# 4-layer-microstrip-nomask-osh.net
KiCad netlist of a schematic drawn in EAGLE
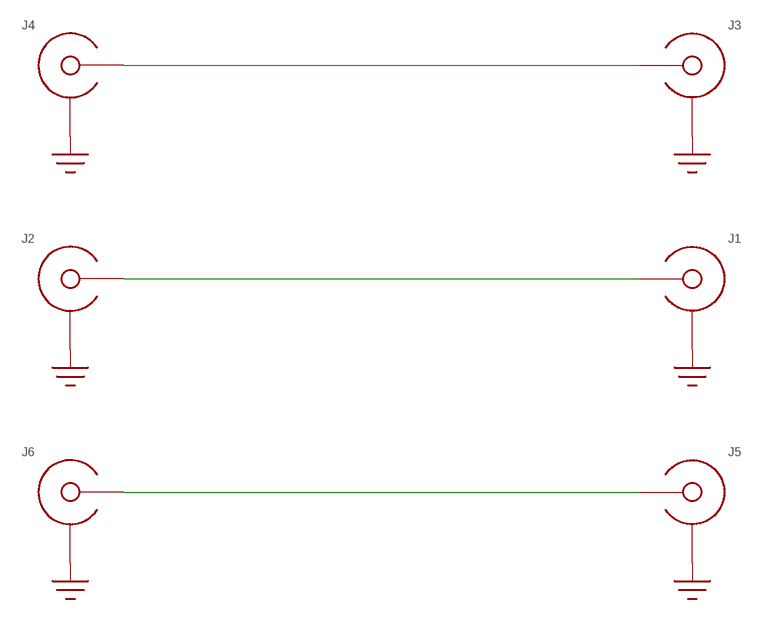
[diagram p0: schematic, sheet 1]

(export (version "E")
  (design (tool "Eeschema 10.0.6"))
  (components
    (comp (ref "J1")
      (value "SMA-EDGE-LAUNCH4L-4020-TAPER-FIXED")
      (footprint "eagle-import:SMA_EDGE_LAUNCH_4L_4020_TAPER_FIXED")
      (libsource (lib "eagle-import") (part "SMA-EDGE-LAUNCH4L-4020-TAPER-FIXED"))
    )
    (comp (ref "J2")
      (value "SMA-EDGE-LAUNCH4L-4020-TAPER-FIXED")
      (footprint "eagle-import:SMA_EDGE_LAUNCH_4L_4020_TAPER_FIXED")
      (libsource (lib "eagle-import") (part "SMA-EDGE-LAUNCH4L-4020-TAPER-FIXED"))
    )
    (comp (ref "J3")
      (value "SMA-EDGE-LAUNCH4L-4020-TAPER-FIXED")
      (footprint "eagle-import:SMA_EDGE_LAUNCH_4L_4020_TAPER_FIXED")
      (libsource (lib "eagle-import") (part "SMA-EDGE-LAUNCH4L-4020-TAPER-FIXED"))
    )
    (comp (ref "J4")
      (value "SMA-EDGE-LAUNCH4L-4020-TAPER-FIXED")
      (footprint "eagle-import:SMA_EDGE_LAUNCH_4L_4020_TAPER_FIXED")
      (libsource (lib "eagle-import") (part "SMA-EDGE-LAUNCH4L-4020-TAPER-FIXED"))
    )
    (comp (ref "J5")
      (value "SMA-EDGE-LAUNCH4L-4020-TAPER-FIXED")
      (footprint "eagle-import:SMA_EDGE_LAUNCH_4L_4020_TAPER_FIXED")
      (libsource (lib "eagle-import") (part "SMA-EDGE-LAUNCH4L-4020-TAPER-FIXED"))
    )
    (comp (ref "J6")
      (value "SMA-EDGE-LAUNCH4L-4020-TAPER-FIXED")
      (footprint "eagle-import:SMA_EDGE_LAUNCH_4L_4020_TAPER_FIXED")
      (libsource (lib "eagle-import") (part "SMA-EDGE-LAUNCH4L-4020-TAPER-FIXED"))
    )
  )
  (nets
    (net (code "1") (name "GND") (class "Default")
      (node (ref "J1") (pin "BOTTOM_GND") (pinfunction "SHIELD_BOTTOM_GND") (pintype "bidirectional"))
      (node (ref "J1") (pin "GND@1") (pinfunction "SHIELD_GND@1") (pintype "bidirectional"))
      (node (ref "J1") (pin "GND@14") (pinfunction "SHIELD_GND@14") (pintype "bidirectional"))
      (node (ref "J1") (pin "GND@15") (pinfunction "SHIELD_GND@15") (pintype "bidirectional"))
      (node (ref "J1") (pin "GND@16") (pinfunction "SHIELD_GND@16") (pintype "bidirectional"))
      (node (ref "J1") (pin "GND@17") (pinfunction "SHIELD_GND@17") (pintype "bidirectional"))
      (node (ref "J1") (pin "GND@2") (pinfunction "SHIELD_GND@2") (pintype "bidirectional"))
      (node (ref "J1") (pin "GND@3") (pinfunction "SHIELD_GND@3") (pintype "bidirectional"))
      (node (ref "J1") (pin "GND@4") (pinfunction "SHIELD_GND@4") (pintype "bidirectional"))
      (node (ref "J1") (pin "GND@5") (pinfunction "SHIELD_GND@5") (pintype "bidirectional"))
      (node (ref "J1") (pin "GND@6") (pinfunction "SHIELD_GND@6") (pintype "bidirectional"))
      (node (ref "J1") (pin "GND@7") (pinfunction "SHIELD_GND@7") (pintype "bidirectional"))
      (node (ref "J1") (pin "GND@8") (pinfunction "SHIELD_GND@8") (pintype "bidirectional"))
      (node (ref "J1") (pin "GND_PAD1") (pinfunction "SHIELD_GND_PAD1") (pintype "bidirectional"))
      (node (ref "J1") (pin "GND_PAD2") (pinfunction "SHIELD_GND_PAD2") (pintype "bidirectional"))
      (node (ref "J1") (pin "P$1") (pinfunction "SHIELD_P$1") (pintype "bidirectional"))
      (node (ref "J1") (pin "P$2") (pinfunction "SHIELD_P$2") (pintype "bidirectional"))
      (node (ref "J2") (pin "BOTTOM_GND") (pinfunction "SHIELD_BOTTOM_GND") (pintype "bidirectional"))
      (node (ref "J2") (pin "GND@1") (pinfunction "SHIELD_GND@1") (pintype "bidirectional"))
      (node (ref "J2") (pin "GND@14") (pinfunction "SHIELD_GND@14") (pintype "bidirectional"))
      (node (ref "J2") (pin "GND@15") (pinfunction "SHIELD_GND@15") (pintype "bidirectional"))
      (node (ref "J2") (pin "GND@16") (pinfunction "SHIELD_GND@16") (pintype "bidirectional"))
      (node (ref "J2") (pin "GND@17") (pinfunction "SHIELD_GND@17") (pintype "bidirectional"))
      (node (ref "J2") (pin "GND@2") (pinfunction "SHIELD_GND@2") (pintype "bidirectional"))
      (node (ref "J2") (pin "GND@3") (pinfunction "SHIELD_GND@3") (pintype "bidirectional"))
      (node (ref "J2") (pin "GND@4") (pinfunction "SHIELD_GND@4") (pintype "bidirectional"))
      (node (ref "J2") (pin "GND@5") (pinfunction "SHIELD_GND@5") (pintype "bidirectional"))
      (node (ref "J2") (pin "GND@6") (pinfunction "SHIELD_GND@6") (pintype "bidirectional"))
      (node (ref "J2") (pin "GND@7") (pinfunction "SHIELD_GND@7") (pintype "bidirectional"))
      (node (ref "J2") (pin "GND@8") (pinfunction "SHIELD_GND@8") (pintype "bidirectional"))
      (node (ref "J2") (pin "GND_PAD1") (pinfunction "SHIELD_GND_PAD1") (pintype "bidirectional"))
      (node (ref "J2") (pin "GND_PAD2") (pinfunction "SHIELD_GND_PAD2") (pintype "bidirectional"))
      (node (ref "J2") (pin "P$1") (pinfunction "SHIELD_P$1") (pintype "bidirectional"))
      (node (ref "J2") (pin "P$2") (pinfunction "SHIELD_P$2") (pintype "bidirectional"))
      (node (ref "J3") (pin "BOTTOM_GND") (pinfunction "SHIELD_BOTTOM_GND") (pintype "bidirectional"))
      (node (ref "J3") (pin "GND@1") (pinfunction "SHIELD_GND@1") (pintype "bidirectional"))
      (node (ref "J3") (pin "GND@14") (pinfunction "SHIELD_GND@14") (pintype "bidirectional"))
      (node (ref "J3") (pin "GND@15") (pinfunction "SHIELD_GND@15") (pintype "bidirectional"))
      (node (ref "J3") (pin "GND@16") (pinfunction "SHIELD_GND@16") (pintype "bidirectional"))
      (node (ref "J3") (pin "GND@17") (pinfunction "SHIELD_GND@17") (pintype "bidirectional"))
      (node (ref "J3") (pin "GND@2") (pinfunction "SHIELD_GND@2") (pintype "bidirectional"))
      (node (ref "J3") (pin "GND@3") (pinfunction "SHIELD_GND@3") (pintype "bidirectional"))
      (node (ref "J3") (pin "GND@4") (pinfunction "SHIELD_GND@4") (pintype "bidirectional"))
      (node (ref "J3") (pin "GND@5") (pinfunction "SHIELD_GND@5") (pintype "bidirectional"))
      (node (ref "J3") (pin "GND@6") (pinfunction "SHIELD_GND@6") (pintype "bidirectional"))
      (node (ref "J3") (pin "GND@7") (pinfunction "SHIELD_GND@7") (pintype "bidirectional"))
      (node (ref "J3") (pin "GND@8") (pinfunction "SHIELD_GND@8") (pintype "bidirectional"))
      (node (ref "J3") (pin "GND_PAD1") (pinfunction "SHIELD_GND_PAD1") (pintype "bidirectional"))
      (node (ref "J3") (pin "GND_PAD2") (pinfunction "SHIELD_GND_PAD2") (pintype "bidirectional"))
      (node (ref "J3") (pin "P$1") (pinfunction "SHIELD_P$1") (pintype "bidirectional"))
      (node (ref "J3") (pin "P$2") (pinfunction "SHIELD_P$2") (pintype "bidirectional"))
      (node (ref "J4") (pin "BOTTOM_GND") (pinfunction "SHIELD_BOTTOM_GND") (pintype "bidirectional"))
      (node (ref "J4") (pin "GND@1") (pinfunction "SHIELD_GND@1") (pintype "bidirectional"))
      (node (ref "J4") (pin "GND@14") (pinfunction "SHIELD_GND@14") (pintype "bidirectional"))
      (node (ref "J4") (pin "GND@15") (pinfunction "SHIELD_GND@15") (pintype "bidirectional"))
      (node (ref "J4") (pin "GND@16") (pinfunction "SHIELD_GND@16") (pintype "bidirectional"))
      (node (ref "J4") (pin "GND@17") (pinfunction "SHIELD_GND@17") (pintype "bidirectional"))
      (node (ref "J4") (pin "GND@2") (pinfunction "SHIELD_GND@2") (pintype "bidirectional"))
      (node (ref "J4") (pin "GND@3") (pinfunction "SHIELD_GND@3") (pintype "bidirectional"))
      (node (ref "J4") (pin "GND@4") (pinfunction "SHIELD_GND@4") (pintype "bidirectional"))
      (node (ref "J4") (pin "GND@5") (pinfunction "SHIELD_GND@5") (pintype "bidirectional"))
      (node (ref "J4") (pin "GND@6") (pinfunction "SHIELD_GND@6") (pintype "bidirectional"))
      (node (ref "J4") (pin "GND@7") (pinfunction "SHIELD_GND@7") (pintype "bidirectional"))
      (node (ref "J4") (pin "GND@8") (pinfunction "SHIELD_GND@8") (pintype "bidirectional"))
      (node (ref "J4") (pin "GND_PAD1") (pinfunction "SHIELD_GND_PAD1") (pintype "bidirectional"))
      (node (ref "J4") (pin "GND_PAD2") (pinfunction "SHIELD_GND_PAD2") (pintype "bidirectional"))
      (node (ref "J4") (pin "P$1") (pinfunction "SHIELD_P$1") (pintype "bidirectional"))
      (node (ref "J4") (pin "P$2") (pinfunction "SHIELD_P$2") (pintype "bidirectional"))
      (node (ref "J5") (pin "BOTTOM_GND") (pinfunction "SHIELD_BOTTOM_GND") (pintype "bidirectional"))
      (node (ref "J5") (pin "GND@1") (pinfunction "SHIELD_GND@1") (pintype "bidirectional"))
      (node (ref "J5") (pin "GND@14") (pinfunction "SHIELD_GND@14") (pintype "bidirectional"))
      (node (ref "J5") (pin "GND@15") (pinfunction "SHIELD_GND@15") (pintype "bidirectional"))
      (node (ref "J5") (pin "GND@16") (pinfunction "SHIELD_GND@16") (pintype "bidirectional"))
      (node (ref "J5") (pin "GND@17") (pinfunction "SHIELD_GND@17") (pintype "bidirectional"))
      (node (ref "J5") (pin "GND@2") (pinfunction "SHIELD_GND@2") (pintype "bidirectional"))
      (node (ref "J5") (pin "GND@3") (pinfunction "SHIELD_GND@3") (pintype "bidirectional"))
      (node (ref "J5") (pin "GND@4") (pinfunction "SHIELD_GND@4") (pintype "bidirectional"))
      (node (ref "J5") (pin "GND@5") (pinfunction "SHIELD_GND@5") (pintype "bidirectional"))
      (node (ref "J5") (pin "GND@6") (pinfunction "SHIELD_GND@6") (pintype "bidirectional"))
      (node (ref "J5") (pin "GND@7") (pinfunction "SHIELD_GND@7") (pintype "bidirectional"))
      (node (ref "J5") (pin "GND@8") (pinfunction "SHIELD_GND@8") (pintype "bidirectional"))
      (node (ref "J5") (pin "GND_PAD1") (pinfunction "SHIELD_GND_PAD1") (pintype "bidirectional"))
      (node (ref "J5") (pin "GND_PAD2") (pinfunction "SHIELD_GND_PAD2") (pintype "bidirectional"))
      (node (ref "J5") (pin "P$1") (pinfunction "SHIELD_P$1") (pintype "bidirectional"))
      (node (ref "J5") (pin "P$2") (pinfunction "SHIELD_P$2") (pintype "bidirectional"))
      (node (ref "J6") (pin "BOTTOM_GND") (pinfunction "SHIELD_BOTTOM_GND") (pintype "bidirectional"))
      (node (ref "J6") (pin "GND@1") (pinfunction "SHIELD_GND@1") (pintype "bidirectional"))
      (node (ref "J6") (pin "GND@14") (pinfunction "SHIELD_GND@14") (pintype "bidirectional"))
      (node (ref "J6") (pin "GND@15") (pinfunction "SHIELD_GND@15") (pintype "bidirectional"))
      (node (ref "J6") (pin "GND@16") (pinfunction "SHIELD_GND@16") (pintype "bidirectional"))
      (node (ref "J6") (pin "GND@17") (pinfunction "SHIELD_GND@17") (pintype "bidirectional"))
      (node (ref "J6") (pin "GND@2") (pinfunction "SHIELD_GND@2") (pintype "bidirectional"))
      (node (ref "J6") (pin "GND@3") (pinfunction "SHIELD_GND@3") (pintype "bidirectional"))
      (node (ref "J6") (pin "GND@4") (pinfunction "SHIELD_GND@4") (pintype "bidirectional"))
      (node (ref "J6") (pin "GND@5") (pinfunction "SHIELD_GND@5") (pintype "bidirectional"))
      (node (ref "J6") (pin "GND@6") (pinfunction "SHIELD_GND@6") (pintype "bidirectional"))
      (node (ref "J6") (pin "GND@7") (pinfunction "SHIELD_GND@7") (pintype "bidirectional"))
      (node (ref "J6") (pin "GND@8") (pinfunction "SHIELD_GND@8") (pintype "bidirectional"))
      (node (ref "J6") (pin "GND_PAD1") (pinfunction "SHIELD_GND_PAD1") (pintype "bidirectional"))
      (node (ref "J6") (pin "GND_PAD2") (pinfunction "SHIELD_GND_PAD2") (pintype "bidirectional"))
      (node (ref "J6") (pin "P$1") (pinfunction "SHIELD_P$1") (pintype "bidirectional"))
      (node (ref "J6") (pin "P$2") (pinfunction "SHIELD_P$2") (pintype "bidirectional"))
    )
    (net (code "2") (name "Net-(J1-CENTER-PadCENTER@1)") (class "Default")
      (node (ref "J1") (pin "CENTER@1") (pinfunction "CENTER_CENTER@1") (pintype "bidirectional"))
      (node (ref "J1") (pin "P$3") (pinfunction "CENTER_P$3") (pintype "bidirectional"))
      (node (ref "J2") (pin "CENTER@1") (pinfunction "CENTER_CENTER@1") (pintype "bidirectional"))
      (node (ref "J2") (pin "P$3") (pinfunction "CENTER_P$3") (pintype "bidirectional"))
    )
    (net (code "3") (name "Net-(J3-CENTER-PadCENTER@1)") (class "Default")
      (node (ref "J3") (pin "CENTER@1") (pinfunction "CENTER_CENTER@1") (pintype "bidirectional"))
      (node (ref "J3") (pin "P$3") (pinfunction "CENTER_P$3") (pintype "bidirectional"))
      (node (ref "J4") (pin "CENTER@1") (pinfunction "CENTER_CENTER@1") (pintype "bidirectional"))
      (node (ref "J4") (pin "P$3") (pinfunction "CENTER_P$3") (pintype "bidirectional"))
    )
    (net (code "4") (name "Net-(J5-CENTER-PadCENTER@1)") (class "Default")
      (node (ref "J5") (pin "CENTER@1") (pinfunction "CENTER_CENTER@1") (pintype "bidirectional"))
      (node (ref "J5") (pin "P$3") (pinfunction "CENTER_P$3") (pintype "bidirectional"))
      (node (ref "J6") (pin "CENTER@1") (pinfunction "CENTER_CENTER@1") (pintype "bidirectional"))
      (node (ref "J6") (pin "P$3") (pinfunction "CENTER_P$3") (pintype "bidirectional"))
    )
  )
)
